# rs485.net
KiCad netlist of a schematic drawn in Altium Designer
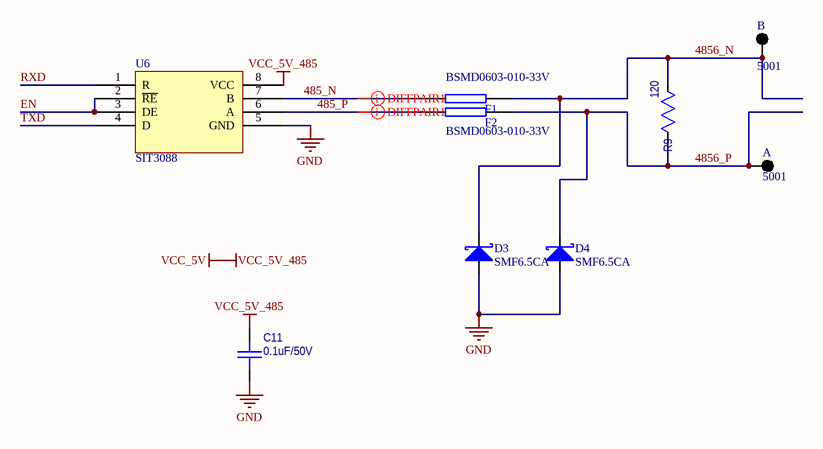
[diagram p0: rs485.SchDoc]

(export (version "E")
  (design (tool "Eeschema 10.0.6"))
  (components
    (comp (ref "A")
      (value "5001")
      (footprint "KSTN-5001")
      (description "Test Point, Black, 1-Pin THD, RoHS, Bulk")
      (fields (field (name "MANUFACTURER") "Keystone"))
      (libsource (lib "Bogen") (part "5001"))
    )
    (comp (ref "B")
      (value "5001")
      (footprint "KSTN-5001")
      (description "Test Point, Black, 1-Pin THD, RoHS, Bulk")
      (fields (field (name "MANUFACTURER") "Keystone"))
      (libsource (lib "Bogen") (part "5001"))
    )
    (comp (ref "C11")
      (value "0.1uF/50V")
      (footprint "CAPC1608X092N_0603")
      (description "Capacitor, MLCC")
      (fields (field (name "MANUFACTURER") "KEMET") (field (name "PARTNUMBER") "C0603C104M5RACTU"))
      (libsource (lib "Karl") (part "Capacitor_0603"))
    )
    (comp (ref "D3") (value "SMF6.5CA") (footprint "SOD123") (libsource (lib "*") (part "DIODE S")))
    (comp (ref "D4") (value "SMF6.5CA") (footprint "SOD123") (libsource (lib "*") (part "DIODE S")))
    (comp (ref "F1") (value "BSMD0603-010-33V") (footprint "0603R") (libsource (lib "*") (part "RES2")))
    (comp (ref "F2") (value "BSMD0603-010-33V") (footprint "0603R") (libsource (lib "*") (part "RES2")))
    (comp (ref "R9")
      (value "120")
      (footprint "RESC1608X055N_0603")
      (description "Resistor, Standard")
      (fields (field (name "MANUFACTURER") "Yageo") (field (name "PARTNUMBER") "RC0603FR-1075KL"))
      (libsource (lib "Karl") (part "Resistor_0603"))
    )
    (comp (ref "U6") (value "SIT3088") (footprint "so-8") (libsource (lib "Schlib1") (part "SN65HVD06D")))
  )
  (nets
    (net (code "1") (name "/485_N") (class "Default")
      (node (ref "F1") (pin "2") (pinfunction "2_2") (pintype "passive"))
      (node (ref "U6") (pin "7") (pinfunction "B_7") (pintype "passive"))
    )
    (net (code "2") (name "/485_P") (class "Default")
      (node (ref "F2") (pin "2") (pinfunction "2_2") (pintype "passive"))
      (node (ref "U6") (pin "6") (pinfunction "A_6") (pintype "passive"))
    )
    (net (code "3") (name "/4856_N") (class "Default")
      (node (ref "B") (pin "1") (pintype "passive"))
      (node (ref "D3") (pin "2") (pinfunction "K_2") (pintype "passive"))
      (node (ref "F1") (pin "1") (pinfunction "1_1") (pintype "passive"))
      (node (ref "R9") (pin "1") (pinfunction "1_1") (pintype "passive"))
    )
    (net (code "4") (name "/4856_P") (class "Default")
      (node (ref "A") (pin "1") (pintype "passive"))
      (node (ref "D4") (pin "2") (pinfunction "K_2") (pintype "passive"))
      (node (ref "F2") (pin "1") (pinfunction "1_1") (pintype "passive"))
      (node (ref "R9") (pin "2") (pinfunction "2_2") (pintype "passive"))
    )
    (net (code "5") (name "/EN") (class "Default")
      (node (ref "U6") (pin "2") (pinfunction "~{RE}_2") (pintype "passive"))
      (node (ref "U6") (pin "3") (pinfunction "DE_3") (pintype "passive"))
    )
    (net (code "6") (name "/RXD") (class "Default")
      (node (ref "U6") (pin "1") (pinfunction "R_1") (pintype "passive"))
    )
    (net (code "7") (name "/TXD") (class "Default")
      (node (ref "U6") (pin "4") (pinfunction "D_4") (pintype "passive"))
    )
    (net (code "8") (name "GND") (class "Default")
      (node (ref "C11") (pin "2") (pinfunction "2_2") (pintype "passive"))
      (node (ref "D3") (pin "1") (pinfunction "A_1") (pintype "passive"))
      (node (ref "D4") (pin "1") (pinfunction "A_1") (pintype "passive"))
      (node (ref "U6") (pin "5") (pinfunction "GND_5") (pintype "passive"))
    )
    (net (code "9") (name "VCC_5V") (class "Default")
      (node (ref "C11") (pin "1") (pinfunction "1_1") (pintype "passive"))
      (node (ref "U6") (pin "8") (pinfunction "VCC_8") (pintype "passive"))
    )
  )
)
